# UltiMem64_Color.net
KiCad netlist of a schematic drawn in EAGLE
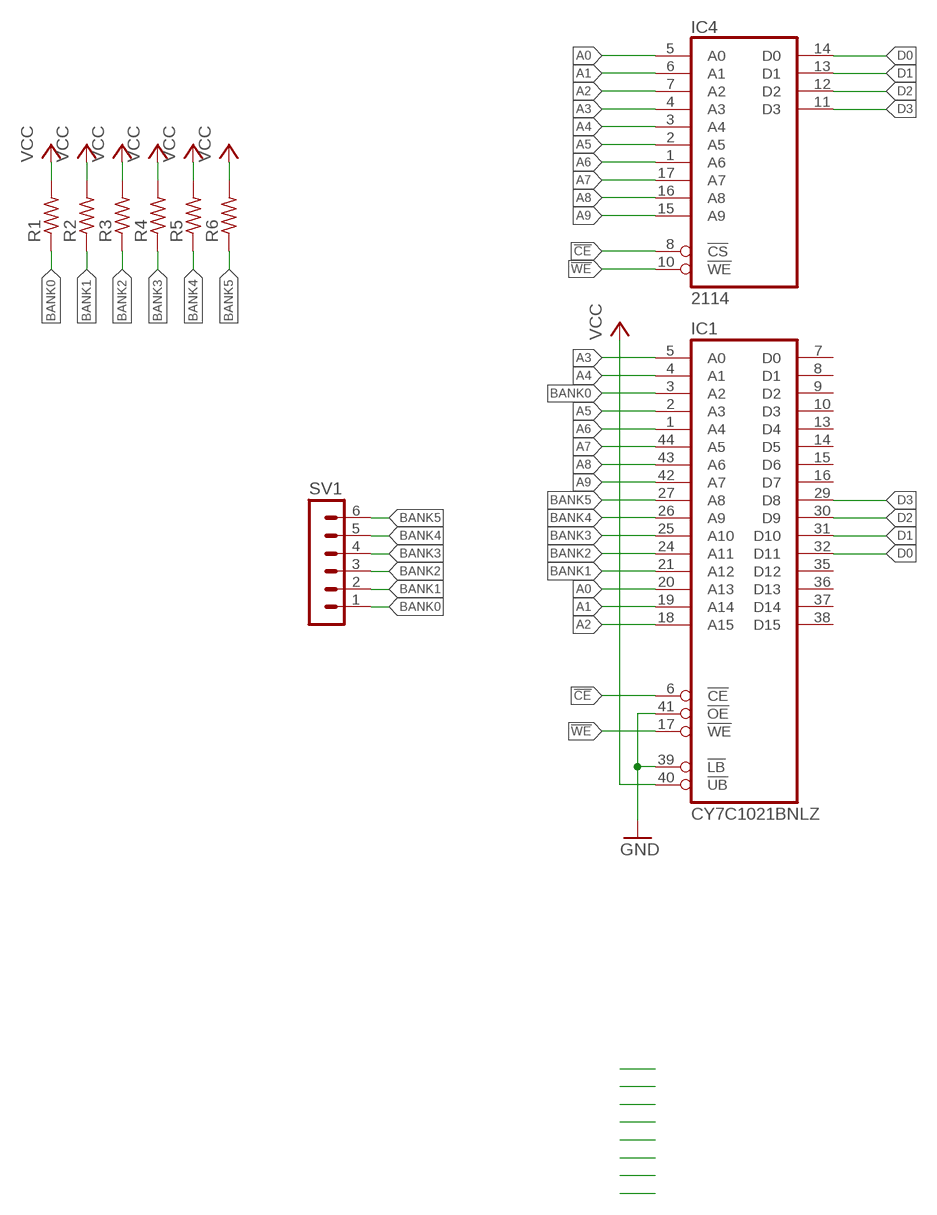
[diagram p0: schematic, sheet 1]

(export (version "E")
  (design (tool "Eeschema 10.0.6"))
  (components
    (comp (ref "IC1")
      (value "CY7C1021BNLZ")
      (footprint "eagle-import:TSOP44-II")
      (libsource (lib "eagle-import") (part "CY7C1021BNLZ"))
    )
    (comp (ref "IC4")
      (value "2114")
      (footprint "eagle-import:DIL18-SMD-REVERSE")
      (libsource (lib "eagle-import") (part "2114-S"))
    )
    (comp (ref "R1")
      (value "R-US_R0402")
      (footprint "eagle-import:R0402")
      (libsource (lib "eagle-import") (part "R-US_R0402"))
    )
    (comp (ref "R2")
      (value "R-US_R0402")
      (footprint "eagle-import:R0402")
      (libsource (lib "eagle-import") (part "R-US_R0402"))
    )
    (comp (ref "R3")
      (value "R-US_R0402")
      (footprint "eagle-import:R0402")
      (libsource (lib "eagle-import") (part "R-US_R0402"))
    )
    (comp (ref "R4")
      (value "R-US_R0402")
      (footprint "eagle-import:R0402")
      (libsource (lib "eagle-import") (part "R-US_R0402"))
    )
    (comp (ref "R5")
      (value "R-US_R0402")
      (footprint "eagle-import:R0402")
      (libsource (lib "eagle-import") (part "R-US_R0402"))
    )
    (comp (ref "R6")
      (value "R-US_R0402")
      (footprint "eagle-import:R0402")
      (libsource (lib "eagle-import") (part "R-US_R0402"))
    )
    (comp (ref "SV1")
      (value "MA06-1")
      (footprint "eagle-import:MA06-1")
      (libsource (lib "eagle-import") (part "MA06-1"))
    )
  )
  (nets
    (net (code "1") (name "/~{CE}") (class "Default")
      (node (ref "IC1") (pin "6") (pinfunction "~{CE}_6") (pintype "input"))
      (node (ref "IC4") (pin "8") (pinfunction "~{CS}_8") (pintype "input"))
    )
    (net (code "2") (name "/~{WE}") (class "Default")
      (node (ref "IC1") (pin "17") (pinfunction "~{WE}_17") (pintype "input"))
      (node (ref "IC4") (pin "10") (pinfunction "~{WE}_10") (pintype "input"))
    )
    (net (code "3") (name "A0") (class "Default")
      (node (ref "IC1") (pin "20") (pinfunction "A13_20") (pintype "input"))
      (node (ref "IC4") (pin "5") (pinfunction "A0_5") (pintype "input"))
    )
    (net (code "4") (name "A1") (class "Default")
      (node (ref "IC1") (pin "19") (pinfunction "A14_19") (pintype "input"))
      (node (ref "IC4") (pin "6") (pinfunction "A1_6") (pintype "input"))
    )
    (net (code "5") (name "A2") (class "Default")
      (node (ref "IC1") (pin "18") (pinfunction "A15_18") (pintype "input"))
      (node (ref "IC4") (pin "7") (pinfunction "A2_7") (pintype "input"))
    )
    (net (code "6") (name "A3") (class "Default")
      (node (ref "IC1") (pin "5") (pinfunction "A0_5") (pintype "input"))
      (node (ref "IC4") (pin "4") (pinfunction "A3_4") (pintype "input"))
    )
    (net (code "7") (name "A4") (class "Default")
      (node (ref "IC1") (pin "4") (pinfunction "A1_4") (pintype "input"))
      (node (ref "IC4") (pin "3") (pinfunction "A4_3") (pintype "input"))
    )
    (net (code "8") (name "A5") (class "Default")
      (node (ref "IC1") (pin "2") (pinfunction "A3_2") (pintype "input"))
      (node (ref "IC4") (pin "2") (pinfunction "A5_2") (pintype "input"))
    )
    (net (code "9") (name "A6") (class "Default")
      (node (ref "IC1") (pin "1") (pinfunction "A4_1") (pintype "input"))
      (node (ref "IC4") (pin "1") (pinfunction "A6_1") (pintype "input"))
    )
    (net (code "10") (name "A7") (class "Default")
      (node (ref "IC1") (pin "44") (pinfunction "A5_44") (pintype "input"))
      (node (ref "IC4") (pin "17") (pinfunction "A7_17") (pintype "input"))
    )
    (net (code "11") (name "A8") (class "Default")
      (node (ref "IC1") (pin "43") (pinfunction "A6_43") (pintype "input"))
      (node (ref "IC4") (pin "16") (pinfunction "A8_16") (pintype "input"))
    )
    (net (code "12") (name "A9") (class "Default")
      (node (ref "IC1") (pin "42") (pinfunction "A7_42") (pintype "input"))
      (node (ref "IC4") (pin "15") (pinfunction "A9_15") (pintype "input"))
    )
    (net (code "13") (name "BANK0") (class "Default")
      (node (ref "IC1") (pin "3") (pinfunction "A2_3") (pintype "input"))
      (node (ref "R1") (pin "1") (pinfunction "1_1") (pintype "passive"))
      (node (ref "SV1") (pin "1") (pinfunction "1_1") (pintype "passive"))
    )
    (net (code "14") (name "BANK1") (class "Default")
      (node (ref "IC1") (pin "21") (pinfunction "A12_21") (pintype "input"))
      (node (ref "R2") (pin "1") (pinfunction "1_1") (pintype "passive"))
      (node (ref "SV1") (pin "2") (pinfunction "2_2") (pintype "passive"))
    )
    (net (code "15") (name "BANK2") (class "Default")
      (node (ref "IC1") (pin "24") (pinfunction "A11_24") (pintype "input"))
      (node (ref "R3") (pin "1") (pinfunction "1_1") (pintype "passive"))
      (node (ref "SV1") (pin "3") (pinfunction "3_3") (pintype "passive"))
    )
    (net (code "16") (name "BANK3") (class "Default")
      (node (ref "IC1") (pin "25") (pinfunction "A10_25") (pintype "input"))
      (node (ref "R4") (pin "1") (pinfunction "1_1") (pintype "passive"))
      (node (ref "SV1") (pin "4") (pinfunction "4_4") (pintype "passive"))
    )
    (net (code "17") (name "BANK4") (class "Default")
      (node (ref "IC1") (pin "26") (pinfunction "A9_26") (pintype "input"))
      (node (ref "R5") (pin "1") (pinfunction "1_1") (pintype "passive"))
      (node (ref "SV1") (pin "5") (pinfunction "5_5") (pintype "passive"))
    )
    (net (code "18") (name "BANK5") (class "Default")
      (node (ref "IC1") (pin "27") (pinfunction "A8_27") (pintype "input"))
      (node (ref "R6") (pin "1") (pinfunction "1_1") (pintype "passive"))
      (node (ref "SV1") (pin "6") (pinfunction "6_6") (pintype "passive"))
    )
    (net (code "19") (name "D0") (class "Default")
      (node (ref "IC1") (pin "32") (pinfunction "D11_32") (pintype "bidirectional"))
      (node (ref "IC4") (pin "14") (pinfunction "D0_14") (pintype "bidirectional"))
    )
    (net (code "20") (name "D1") (class "Default")
      (node (ref "IC1") (pin "31") (pinfunction "D10_31") (pintype "bidirectional"))
      (node (ref "IC4") (pin "13") (pinfunction "D1_13") (pintype "bidirectional"))
    )
    (net (code "21") (name "D2") (class "Default")
      (node (ref "IC1") (pin "30") (pinfunction "D9_30") (pintype "bidirectional"))
      (node (ref "IC4") (pin "12") (pinfunction "D2_12") (pintype "bidirectional"))
    )
    (net (code "22") (name "D3") (class "Default")
      (node (ref "IC1") (pin "29") (pinfunction "D8_29") (pintype "bidirectional"))
      (node (ref "IC4") (pin "11") (pinfunction "D3_11") (pintype "bidirectional"))
    )
    (net (code "23") (name "GND") (class "Default")
      (node (ref "IC1") (pin "39") (pinfunction "~{LB}_39") (pintype "input"))
      (node (ref "IC1") (pin "41") (pinfunction "~{OE}_41") (pintype "input"))
    )
    (net (code "24") (name "VCC") (class "Default")
      (node (ref "IC1") (pin "40") (pinfunction "~{UB}_40") (pintype "input"))
      (node (ref "R1") (pin "2") (pinfunction "2_2") (pintype "passive"))
      (node (ref "R2") (pin "2") (pinfunction "2_2") (pintype "passive"))
      (node (ref "R3") (pin "2") (pinfunction "2_2") (pintype "passive"))
      (node (ref "R4") (pin "2") (pinfunction "2_2") (pintype "passive"))
      (node (ref "R5") (pin "2") (pinfunction "2_2") (pintype "passive"))
      (node (ref "R6") (pin "2") (pinfunction "2_2") (pintype "passive"))
    )
    (net (code "25") (name "unconnected-(IC1A-D0-Pad7)") (class "Default")
      (node (ref "IC1") (pin "7") (pinfunction "D0_7") (pintype "bidirectional"))
    )
    (net (code "26") (name "unconnected-(IC1A-D1-Pad8)") (class "Default")
      (node (ref "IC1") (pin "8") (pinfunction "D1_8") (pintype "bidirectional"))
    )
    (net (code "27") (name "unconnected-(IC1A-D2-Pad9)") (class "Default")
      (node (ref "IC1") (pin "9") (pinfunction "D2_9") (pintype "bidirectional"))
    )
    (net (code "28") (name "unconnected-(IC1A-D3-Pad10)") (class "Default")
      (node (ref "IC1") (pin "10") (pinfunction "D3_10") (pintype "bidirectional"))
    )
    (net (code "29") (name "unconnected-(IC1A-D4-Pad13)") (class "Default")
      (node (ref "IC1") (pin "13") (pinfunction "D4_13") (pintype "bidirectional"))
    )
    (net (code "30") (name "unconnected-(IC1A-D5-Pad14)") (class "Default")
      (node (ref "IC1") (pin "14") (pinfunction "D5_14") (pintype "bidirectional"))
    )
    (net (code "31") (name "unconnected-(IC1A-D6-Pad15)") (class "Default")
      (node (ref "IC1") (pin "15") (pinfunction "D6_15") (pintype "bidirectional"))
    )
    (net (code "32") (name "unconnected-(IC1A-D7-Pad16)") (class "Default")
      (node (ref "IC1") (pin "16") (pinfunction "D7_16") (pintype "bidirectional"))
    )
    (net (code "33") (name "unconnected-(IC1A-D12-Pad35)") (class "Default")
      (node (ref "IC1") (pin "35") (pinfunction "D12_35") (pintype "bidirectional"))
    )
    (net (code "34") (name "unconnected-(IC1A-D13-Pad36)") (class "Default")
      (node (ref "IC1") (pin "36") (pinfunction "D13_36") (pintype "bidirectional"))
    )
    (net (code "35") (name "unconnected-(IC1A-D14-Pad37)") (class "Default")
      (node (ref "IC1") (pin "37") (pinfunction "D14_37") (pintype "bidirectional"))
    )
    (net (code "36") (name "unconnected-(IC1A-D15-Pad38)") (class "Default")
      (node (ref "IC1") (pin "38") (pinfunction "D15_38") (pintype "bidirectional"))
    )
  )
)
